# beacon.net
KiCad netlist of a schematic drawn in Altium Designer
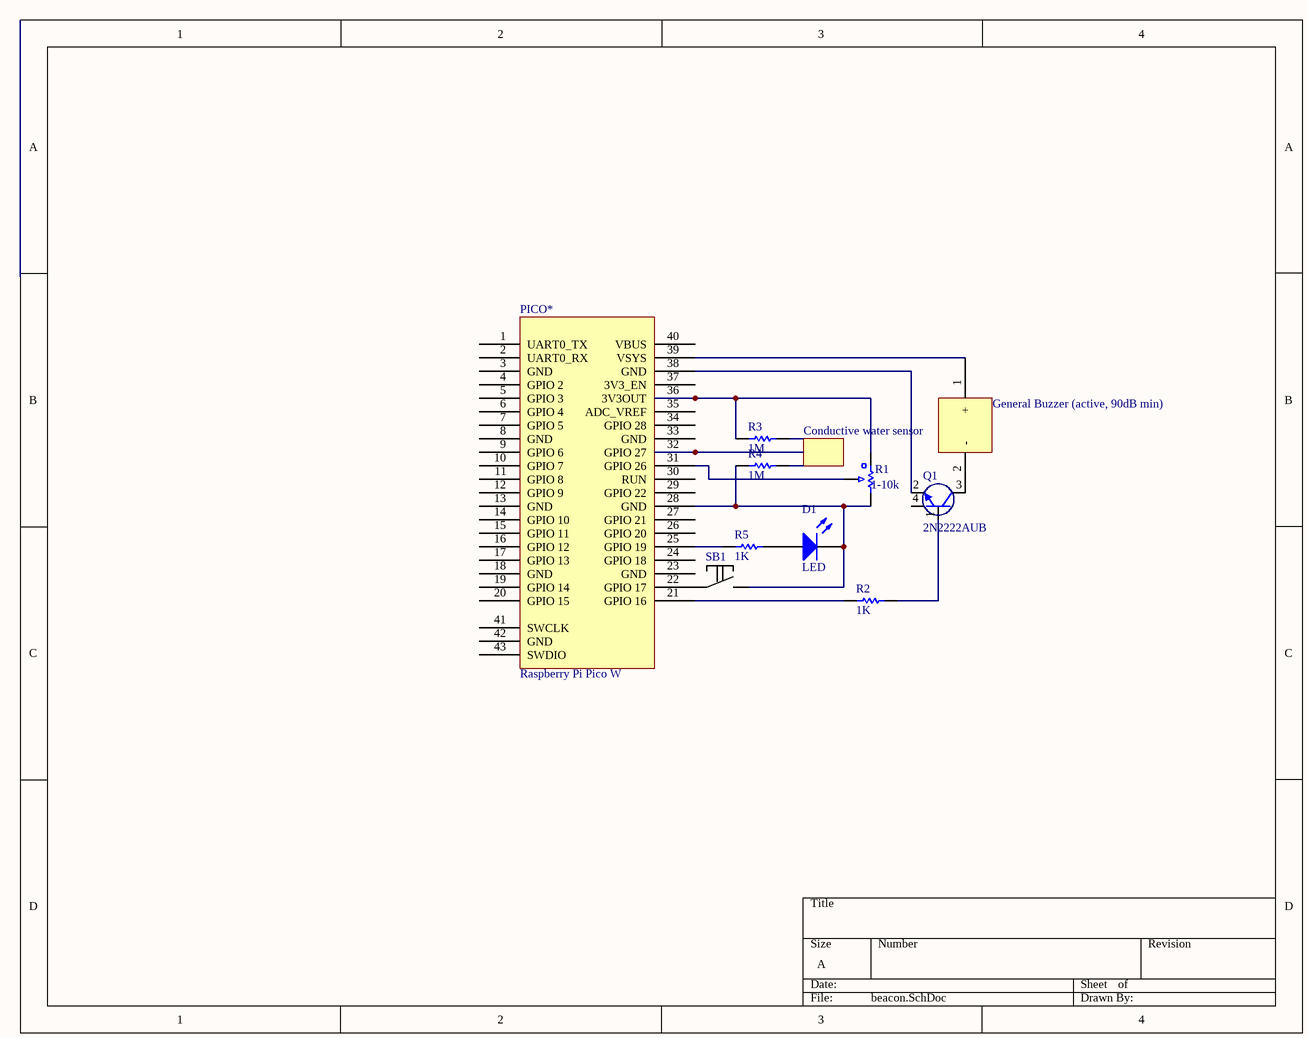
[diagram p0: beacon.SchDoc]

(export (version "E")
  (design (tool "Eeschema 10.0.6"))
  (components
    (comp (ref "D1")
      (value "LED")
      (footprint "PCB-jf8qttwyjk8kzbl8ossh-1")
      (description "LED, Standard throughole Or 0603 SMA")
      (fields (field (name "JLCPCB PART #") "C2895470"))
      (libsource (lib "My Personal Space") (part "SYM-b20d7b0713fb6dca-1"))
    )
    (comp (ref "General Buzzer (active, 90dB min)")
      (value "~")
      (footprint "PCB-xlh7dy84o8mtcso35ftk-1")
      (description "Piezo Buzzer")
      (libsource (lib "My Personal Space") (part "SYM-5fc196cb676b8006-1"))
    )
    (comp (ref "PICO*")
      (value "Raspberry Pi Pico W")
      (footprint "Raspberry Pi RASPBERRY PI PICO W-Footprint-1")
      (description "Raspberry Pi Board, Arm CORTEX-M0+;")
      (fields (field (name "MANUFACTURER PART NUMBER") "RASPBERRY PI PICO W"))
      (libsource (lib "My Personal Space") (part "PinOut"))
    )
    (comp (ref "Q1")
      (value "2N2222AUB")
      (footprint "2N2222AUB-Footprint-1")
      (description "Small Signal Bipolar Transistor, 0.8A I(C), 50V V(BR)CEO, 1-Element, NPN, Silicon")
      (libsource (lib "My Personal Space") (part "SYM-858265-1"))
    )
    (comp (ref "R1")
      (value "1-10k")
      (footprint "PCB-37o3ncptyek4ffexthz2-1")
      (description "Res Conductive Plastic POT 10K Ohm 20% 1/5W 1(Elec)/1(Mech)Turn 6mm Pin Panel Mount/Through Hole")
      (fields
        (field (name "MANUFACTURER") "BI Technologies")
        (field (name "MANUFACTURER PART NUMBER") "P160KN-0QC15B10K")
      )
      (libsource (lib "My Personal Space") (part "SYM-b3177a6863606cd0-1"))
    )
    (comp (ref "R2")
      (value "1K")
      (footprint "0402-RES")
      (description "RESISTOR, 0402, 1K, 0.1%, 0.063W")
      (fields (field (name "MANUFACTURER PART NUMBER") "ERA-2AEB102X"))
      (libsource (lib "My Personal Space") (part "RES-2"))
    )
    (comp (ref "R3")
      (value "1M")
      (footprint "0402-RES")
      (fields (field (name "MANUFACTURER PART NUMBER") "ERA-2AEB102X"))
      (libsource (lib "My Personal Space") (part "RES-2"))
    )
    (comp (ref "R4")
      (value "1M")
      (footprint "0402-RES")
      (fields (field (name "MANUFACTURER PART NUMBER") "ERA-2AEB102X"))
      (libsource (lib "My Personal Space") (part "RES-2"))
    )
    (comp (ref "R5")
      (value "1K")
      (footprint "0402-RES")
      (description "RESISTOR, 0402, 1K, 0.1%, 0.063W")
      (fields (field (name "MANUFACTURER PART NUMBER") "ERA-2AEB102X"))
      (libsource (lib "My Personal Space") (part "RES-2"))
    )
    (comp (ref "SB1")
      (value "~")
      (footprint "PCB-4tdpvsv0cagcn96pionj-1")
      (description "Black Button Tactile Switch, SPST 50 mA@ 24 V dc 1.24mm")
      (fields (field (name "MANUFACTURER PART NUMBER") "FSMRA2JH"))
      (libsource (lib "My Personal Space") (part "SYM-fbb930d55ed6247e-1"))
    )
  )
  (nets
    (net (code "1") (name "Net-(D1-A)") (class "Default")
      (node (ref "D1") (pin "1") (pinfunction "A_1") (pintype "passive"))
      (node (ref "R5") (pin "2") (pinfunction "2_2") (pintype "passive"))
    )
    (net (code "2") (name "Net-(D1-K)") (class "Default")
      (node (ref "D1") (pin "2") (pinfunction "K_2") (pintype "passive"))
      (node (ref "PICO*") (pin "28") (pinfunction "GND_28") (pintype "passive"))
      (node (ref "R1") (pin "3") (pinfunction "3_3") (pintype "passive"))
      (node (ref "R4") (pin "1") (pinfunction "1_1") (pintype "passive"))
      (node (ref "SB1") (pin "2") (pinfunction "2_2") (pintype "passive"))
    )
    (net (code "3") (name "Net-(General Buzzer (active, 90dB min)-+)") (class "Default")
      (node (ref "General Buzzer (active, 90dB min)") (pin "1") (pinfunction "+_1") (pintype "passive"))
      (node (ref "PICO*") (pin "39") (pinfunction "VSYS_39") (pintype "passive"))
    )
    (net (code "4") (name "Net-(General Buzzer (active, 90dB min)--)") (class "Default")
      (node (ref "General Buzzer (active, 90dB min)") (pin "2") (pinfunction "-_2") (pintype "passive"))
      (node (ref "Q1") (pin "3") (pinfunction "C_3") (pintype "passive"))
    )
    (net (code "5") (name "Net-(PICO*-3V3OUT)") (class "Default")
      (node (ref "PICO*") (pin "36") (pinfunction "3V3OUT_36") (pintype "passive"))
      (node (ref "R1") (pin "1") (pinfunction "1_1") (pintype "passive"))
      (node (ref "R3") (pin "1") (pinfunction "1_1") (pintype "passive"))
    )
    (net (code "6") (name "Net-(PICO*-GPIO_16)") (class "Default")
      (node (ref "PICO*") (pin "21") (pinfunction "GPIO_16_21") (pintype "passive"))
      (node (ref "R2") (pin "1") (pinfunction "1_1") (pintype "passive"))
    )
    (net (code "7") (name "Net-(PICO*-GPIO_19)") (class "Default")
      (node (ref "PICO*") (pin "25") (pinfunction "GPIO_19_25") (pintype "passive"))
      (node (ref "R5") (pin "1") (pinfunction "1_1") (pintype "passive"))
    )
    (net (code "8") (name "Net-(PICO*-GPIO_26)") (class "Default")
      (node (ref "PICO*") (pin "31") (pinfunction "GPIO_26_31") (pintype "passive"))
      (node (ref "R1") (pin "2") (pinfunction "2_2") (pintype "passive"))
    )
    (net (code "9") (name "Net-(Q1-B)") (class "Default")
      (node (ref "Q1") (pin "1") (pinfunction "B_1") (pintype "passive"))
      (node (ref "R2") (pin "2") (pinfunction "2_2") (pintype "passive"))
    )
    (net (code "10") (name "Net-(Q1-E)") (class "Default")
      (node (ref "PICO*") (pin "38") (pinfunction "GND_38") (pintype "passive"))
      (node (ref "Q1") (pin "2") (pinfunction "E_2") (pintype "passive"))
    )
    (net (code "11") (name "unconnected-(PICO*-3V3_EN-Pad37)") (class "Default")
      (node (ref "PICO*") (pin "37") (pinfunction "3V3_EN_37") (pintype "passive"))
    )
    (net (code "12") (name "unconnected-(PICO*-ADC_VREF-Pad35)") (class "Default")
      (node (ref "PICO*") (pin "35") (pinfunction "ADC_VREF_35") (pintype "passive"))
    )
    (net (code "13") (name "unconnected-(PICO*-GND-Pad3)") (class "Default")
      (node (ref "PICO*") (pin "3") (pinfunction "GND_3") (pintype "passive"))
    )
    (net (code "14") (name "unconnected-(PICO*-GND-Pad8)") (class "Default")
      (node (ref "PICO*") (pin "8") (pinfunction "GND_8") (pintype "passive"))
    )
    (net (code "15") (name "unconnected-(PICO*-GND-Pad13)") (class "Default")
      (node (ref "PICO*") (pin "13") (pinfunction "GND_13") (pintype "passive"))
    )
    (net (code "16") (name "unconnected-(PICO*-GND-Pad18)") (class "Default")
      (node (ref "PICO*") (pin "18") (pinfunction "GND_18") (pintype "passive"))
    )
    (net (code "17") (name "unconnected-(PICO*-GND-Pad23)") (class "Default")
      (node (ref "PICO*") (pin "23") (pinfunction "GND_23") (pintype "passive"))
    )
    (net (code "18") (name "unconnected-(PICO*-GND-Pad33)") (class "Default")
      (node (ref "PICO*") (pin "33") (pinfunction "GND_33") (pintype "passive"))
    )
    (net (code "19") (name "unconnected-(PICO*-GND-Pad42)") (class "Default")
      (node (ref "PICO*") (pin "42") (pinfunction "GND_42") (pintype "passive"))
    )
    (net (code "20") (name "unconnected-(PICO*-GPIO_2-Pad4)") (class "Default")
      (node (ref "PICO*") (pin "4") (pinfunction "GPIO_2_4") (pintype "passive"))
    )
    (net (code "21") (name "unconnected-(PICO*-GPIO_3-Pad5)") (class "Default")
      (node (ref "PICO*") (pin "5") (pinfunction "GPIO_3_5") (pintype "passive"))
    )
    (net (code "22") (name "unconnected-(PICO*-GPIO_4-Pad6)") (class "Default")
      (node (ref "PICO*") (pin "6") (pinfunction "GPIO_4_6") (pintype "passive"))
    )
    (net (code "23") (name "unconnected-(PICO*-GPIO_5-Pad7)") (class "Default")
      (node (ref "PICO*") (pin "7") (pinfunction "GPIO_5_7") (pintype "passive"))
    )
    (net (code "24") (name "unconnected-(PICO*-GPIO_6-Pad9)") (class "Default")
      (node (ref "PICO*") (pin "9") (pinfunction "GPIO_6_9") (pintype "passive"))
    )
    (net (code "25") (name "unconnected-(PICO*-GPIO_7-Pad10)") (class "Default")
      (node (ref "PICO*") (pin "10") (pinfunction "GPIO_7_10") (pintype "passive"))
    )
    (net (code "26") (name "unconnected-(PICO*-GPIO_8-Pad11)") (class "Default")
      (node (ref "PICO*") (pin "11") (pinfunction "GPIO_8_11") (pintype "passive"))
    )
    (net (code "27") (name "unconnected-(PICO*-GPIO_9-Pad12)") (class "Default")
      (node (ref "PICO*") (pin "12") (pinfunction "GPIO_9_12") (pintype "passive"))
    )
    (net (code "28") (name "unconnected-(PICO*-GPIO_10-Pad14)") (class "Default")
      (node (ref "PICO*") (pin "14") (pinfunction "GPIO_10_14") (pintype "passive"))
    )
    (net (code "29") (name "unconnected-(PICO*-GPIO_11-Pad15)") (class "Default")
      (node (ref "PICO*") (pin "15") (pinfunction "GPIO_11_15") (pintype "passive"))
    )
    (net (code "30") (name "unconnected-(PICO*-GPIO_12-Pad16)") (class "Default")
      (node (ref "PICO*") (pin "16") (pinfunction "GPIO_12_16") (pintype "passive"))
    )
    (net (code "31") (name "unconnected-(PICO*-GPIO_13-Pad17)") (class "Default")
      (node (ref "PICO*") (pin "17") (pinfunction "GPIO_13_17") (pintype "passive"))
    )
    (net (code "32") (name "unconnected-(PICO*-GPIO_14-Pad19)") (class "Default")
      (node (ref "PICO*") (pin "19") (pinfunction "GPIO_14_19") (pintype "passive"))
    )
    (net (code "33") (name "unconnected-(PICO*-GPIO_15-Pad20)") (class "Default")
      (node (ref "PICO*") (pin "20") (pinfunction "GPIO_15_20") (pintype "passive"))
    )
    (net (code "34") (name "unconnected-(PICO*-GPIO_17-Pad22)") (class "Default")
      (node (ref "PICO*") (pin "22") (pinfunction "GPIO_17_22") (pintype "passive"))
    )
    (net (code "35") (name "unconnected-(PICO*-GPIO_18-Pad24)") (class "Default")
      (node (ref "PICO*") (pin "24") (pinfunction "GPIO_18_24") (pintype "passive"))
    )
    (net (code "36") (name "unconnected-(PICO*-GPIO_20-Pad26)") (class "Default")
      (node (ref "PICO*") (pin "26") (pinfunction "GPIO_20_26") (pintype "passive"))
    )
    (net (code "37") (name "unconnected-(PICO*-GPIO_21-Pad27)") (class "Default")
      (node (ref "PICO*") (pin "27") (pinfunction "GPIO_21_27") (pintype "passive"))
    )
    (net (code "38") (name "unconnected-(PICO*-GPIO_22-Pad29)") (class "Default")
      (node (ref "PICO*") (pin "29") (pinfunction "GPIO_22_29") (pintype "passive"))
    )
    (net (code "39") (name "unconnected-(PICO*-GPIO_27-Pad32)") (class "Default")
      (node (ref "PICO*") (pin "32") (pinfunction "GPIO_27_32") (pintype "passive"))
    )
    (net (code "40") (name "unconnected-(PICO*-GPIO_28-Pad34)") (class "Default")
      (node (ref "PICO*") (pin "34") (pinfunction "GPIO_28_34") (pintype "passive"))
    )
    (net (code "41") (name "unconnected-(PICO*-RUN-Pad30)") (class "Default")
      (node (ref "PICO*") (pin "30") (pinfunction "RUN_30") (pintype "passive"))
    )
    (net (code "42") (name "unconnected-(PICO*-SWCLK-Pad41)") (class "Default")
      (node (ref "PICO*") (pin "41") (pinfunction "SWCLK_41") (pintype "passive"))
    )
    (net (code "43") (name "unconnected-(PICO*-SWDIO-Pad43)") (class "Default")
      (node (ref "PICO*") (pin "43") (pinfunction "SWDIO_43") (pintype "passive"))
    )
    (net (code "44") (name "unconnected-(PICO*-UART0_RX-Pad2)") (class "Default")
      (node (ref "PICO*") (pin "2") (pinfunction "UART0_RX_2") (pintype "passive"))
    )
    (net (code "45") (name "unconnected-(PICO*-UART0_TX-Pad1)") (class "Default")
      (node (ref "PICO*") (pin "1") (pinfunction "UART0_TX_1") (pintype "passive"))
    )
    (net (code "46") (name "unconnected-(PICO*-VBUS-Pad40)") (class "Default")
      (node (ref "PICO*") (pin "40") (pinfunction "VBUS_40") (pintype "passive"))
    )
    (net (code "47") (name "unconnected-(Q1-G-Pad4)") (class "Default")
      (node (ref "Q1") (pin "4") (pinfunction "G_4") (pintype "passive"))
    )
    (net (code "48") (name "unconnected-(R3-Pad2)") (class "Default")
      (node (ref "R3") (pin "2") (pinfunction "2_2") (pintype "passive"))
    )
    (net (code "49") (name "unconnected-(R4-Pad2)") (class "Default")
      (node (ref "R4") (pin "2") (pinfunction "2_2") (pintype "passive"))
    )
    (net (code "50") (name "unconnected-(SB1-Pad1)") (class "Default")
      (node (ref "SB1") (pin "1") (pinfunction "1_1") (pintype "passive"))
    )
  )
)
